# Viltrox_L132T_SAMD_Upgrade.net
KiCad netlist of a schematic drawn in EAGLE
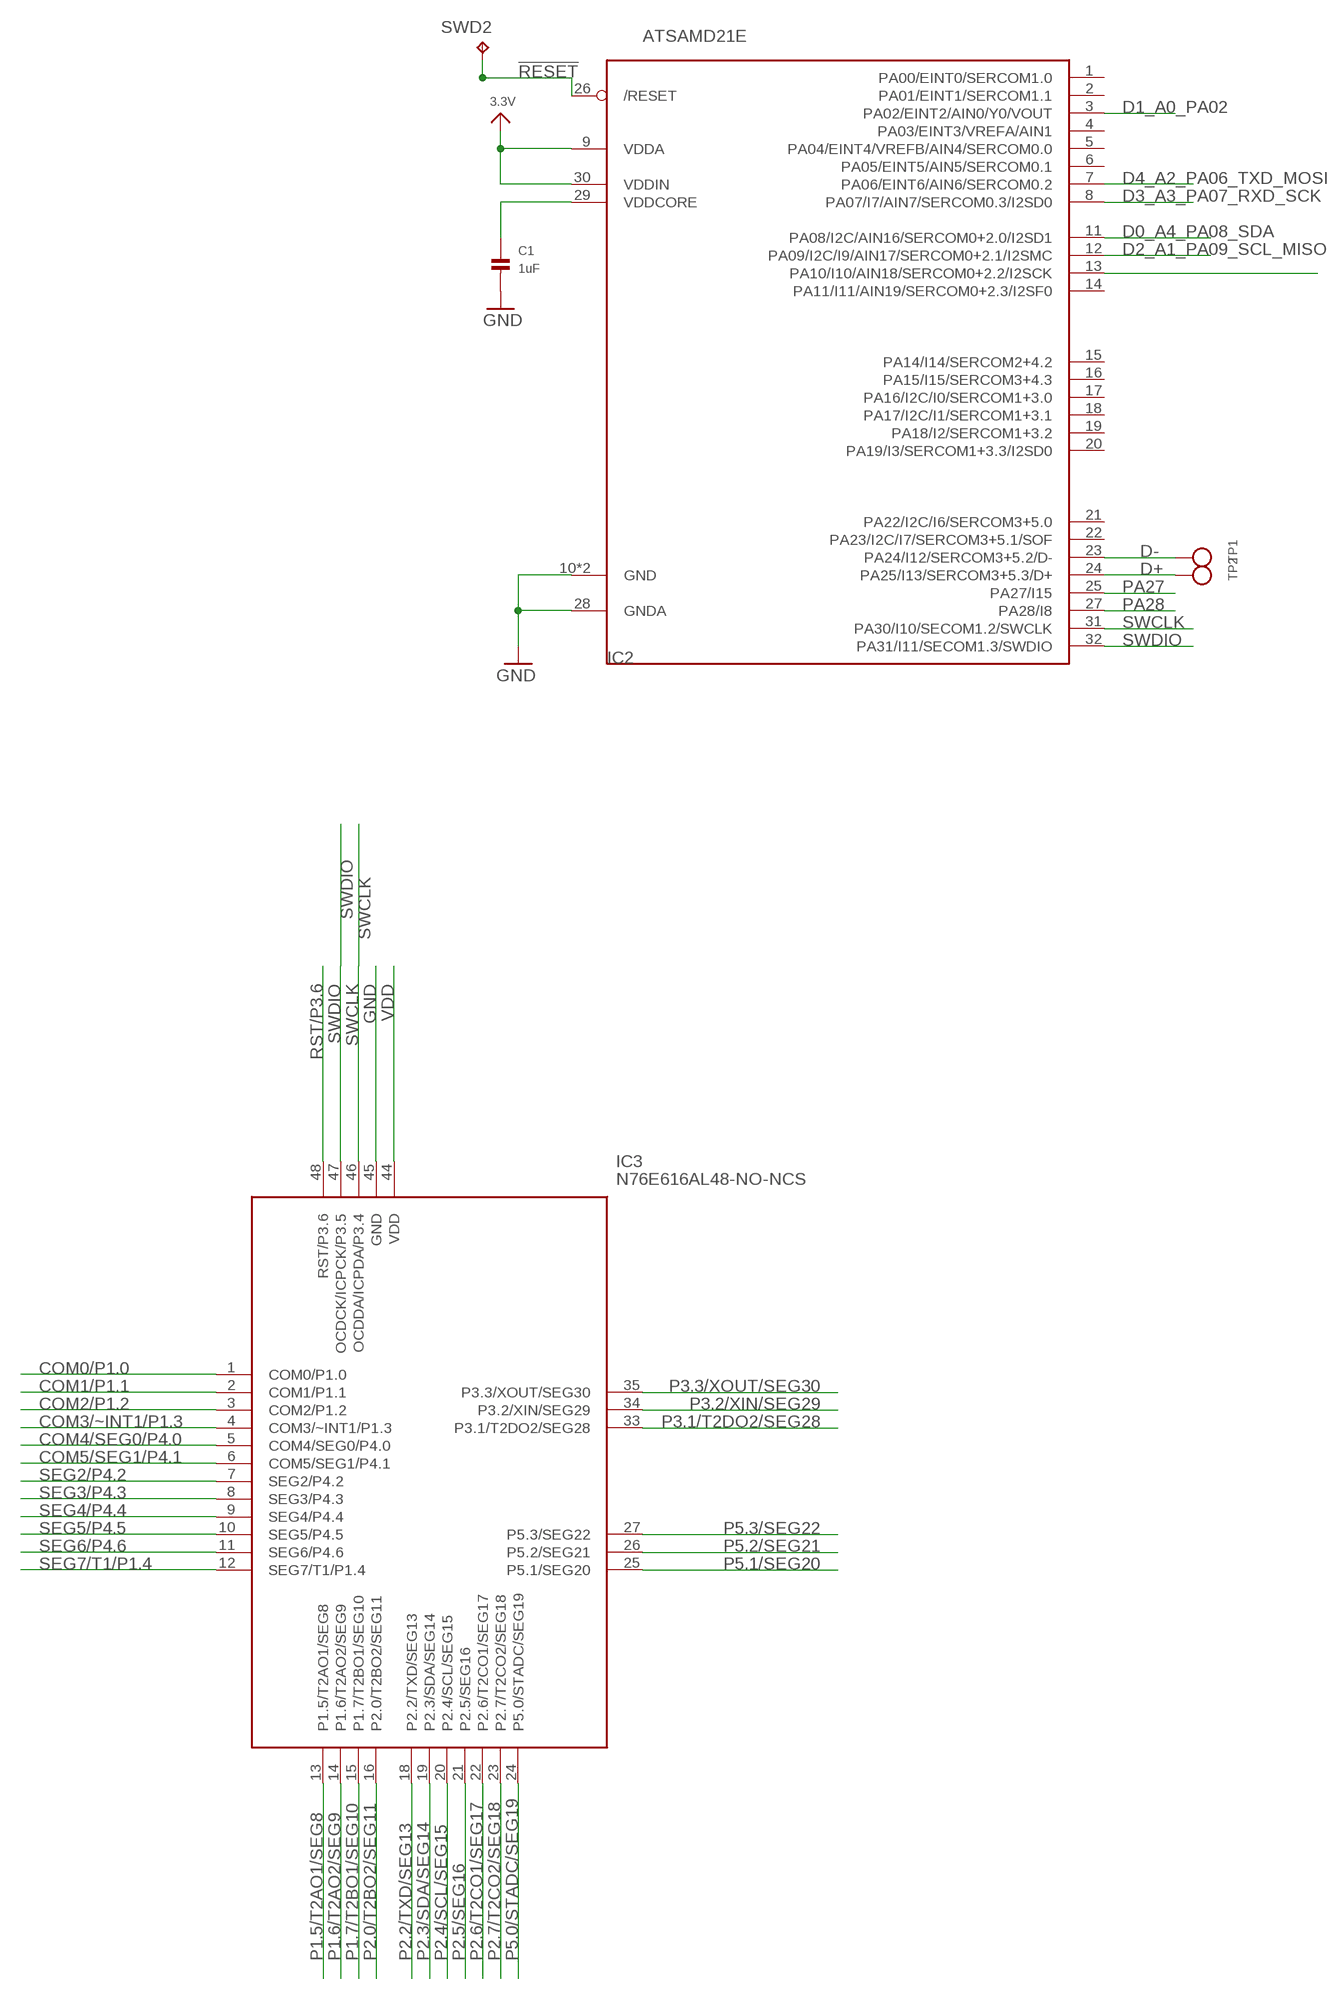
[diagram p0: schematic, sheet 1]

(export (version "E")
  (design (tool "Eeschema 10.0.6"))
  (components
    (comp (ref "C1")
      (value "1uF")
      (footprint "eagle-import:_0402MP")
      (libsource (lib "eagle-import") (part "CAP_CERAMIC_0402MP"))
    )
    (comp (ref "IC2")
      (value "ATSAMD21E")
      (footprint "eagle-import:QFN32_5MM")
      (libsource (lib "eagle-import") (part "ATSAMD21E"))
    )
    (comp (ref "IC3")
      (value "N76E616AL48-NO-NCS")
      (footprint "eagle-import:N76-NO-NC-QFP50P900X900X160-48N")
      (libsource (lib "eagle-import") (part "N76E616AL48-NO-NCS"))
    )
    (comp (ref "SWD2")
      (value "TPB1,27")
      (footprint "eagle-import:B1,27")
      (libsource (lib "eagle-import") (part "TPB1,27"))
    )
    (comp (ref "TP1")
      (value "TESTPOINTROUND2MM")
      (footprint "eagle-import:TESTPOINT_ROUND_2MM")
      (libsource (lib "eagle-import") (part "TESTPOINTROUND2MM"))
    )
    (comp (ref "TP2")
      (value "TESTPOINTROUND2MM")
      (footprint "eagle-import:TESTPOINT_ROUND_2MM")
      (libsource (lib "eagle-import") (part "TESTPOINTROUND2MM"))
    )
  )
  (nets
    (net (code "1") (name "/COM0{slash}P1.0") (class "Default")
      (node (ref "IC3") (pin "1") (pinfunction "COM0/P1.0_1") (pintype "bidirectional"))
    )
    (net (code "2") (name "/COM1{slash}P1.1") (class "Default")
      (node (ref "IC3") (pin "2") (pinfunction "COM1/P1.1_2") (pintype "bidirectional"))
    )
    (net (code "3") (name "/COM2{slash}P1.2") (class "Default")
      (node (ref "IC3") (pin "3") (pinfunction "COM2/P1.2_3") (pintype "bidirectional"))
    )
    (net (code "4") (name "/COM3{slash}~{INT1{slash}P1.3}") (class "Default")
      (node (ref "IC3") (pin "4") (pinfunction "COM3/~{INT1/P1.3}_4") (pintype "bidirectional"))
    )
    (net (code "5") (name "/COM4{slash}SEG0{slash}P4.0") (class "Default")
      (node (ref "IC3") (pin "5") (pinfunction "COM4/SEG0/P4.0_5") (pintype "bidirectional"))
    )
    (net (code "6") (name "/COM5{slash}SEG1{slash}P4.1") (class "Default")
      (node (ref "IC3") (pin "6") (pinfunction "COM5/SEG1/P4.1_6") (pintype "bidirectional"))
    )
    (net (code "7") (name "/D+") (class "Default")
      (node (ref "IC2") (pin "24") (pinfunction "PA25/I13/SERCOM3+5.3/D+_24") (pintype "bidirectional"))
      (node (ref "TP2") (pin "P$1") (pinfunction "P$1_P$1") (pintype "bidirectional"))
    )
    (net (code "8") (name "/D-") (class "Default")
      (node (ref "IC2") (pin "23") (pinfunction "PA24/I12/SERCOM3+5.2/D-_23") (pintype "bidirectional"))
      (node (ref "TP1") (pin "P$1") (pinfunction "P$1_P$1") (pintype "bidirectional"))
    )
    (net (code "9") (name "/D0_A4_PA08_SDA") (class "Default")
      (node (ref "IC2") (pin "11") (pinfunction "PA08/I2C/AIN16/SERCOM0+2.0/I2SD1_11") (pintype "bidirectional"))
    )
    (net (code "10") (name "/D1_A0_PA02") (class "Default")
      (node (ref "IC2") (pin "3") (pinfunction "PA02/EINT2/AIN0/Y0/VOUT_3") (pintype "bidirectional"))
    )
    (net (code "11") (name "/D2_A1_PA09_SCL_MISO") (class "Default")
      (node (ref "IC2") (pin "12") (pinfunction "PA09/I2C/I9/AIN17/SERCOM0+2.1/I2SMC_12") (pintype "bidirectional"))
    )
    (net (code "12") (name "/D3_A3_PA07_RXD_SCK") (class "Default")
      (node (ref "IC2") (pin "8") (pinfunction "PA07/I7/AIN7/SERCOM0.3/I2SD0_8") (pintype "bidirectional"))
    )
    (net (code "13") (name "/D4_A2_PA06_TXD_MOSI") (class "Default")
      (node (ref "IC2") (pin "7") (pinfunction "PA06/EINT6/AIN6/SERCOM0.2_7") (pintype "bidirectional"))
    )
    (net (code "14") (name "/P1.5{slash}T2AO1{slash}SEG8") (class "Default")
      (node (ref "IC3") (pin "13") (pinfunction "P1.5/T2AO1/SEG8_13") (pintype "bidirectional"))
    )
    (net (code "15") (name "/P1.6{slash}T2AO2{slash}SEG9") (class "Default")
      (node (ref "IC3") (pin "14") (pinfunction "P1.6/T2AO2/SEG9_14") (pintype "bidirectional"))
    )
    (net (code "16") (name "/P1.7{slash}T2BO1{slash}SEG10") (class "Default")
      (node (ref "IC3") (pin "15") (pinfunction "P1.7/T2BO1/SEG10_15") (pintype "bidirectional"))
    )
    (net (code "17") (name "/P2.0{slash}T2BO2{slash}SEG11") (class "Default")
      (node (ref "IC3") (pin "16") (pinfunction "P2.0/T2BO2/SEG11_16") (pintype "bidirectional"))
    )
    (net (code "18") (name "/P2.2{slash}TXD{slash}SEG13") (class "Default")
      (node (ref "IC3") (pin "18") (pinfunction "P2.2/TXD/SEG13_18") (pintype "bidirectional"))
    )
    (net (code "19") (name "/P2.3{slash}SDA{slash}SEG14") (class "Default")
      (node (ref "IC3") (pin "19") (pinfunction "P2.3/SDA/SEG14_19") (pintype "bidirectional"))
    )
    (net (code "20") (name "/P2.4{slash}SCL{slash}SEG15") (class "Default")
      (node (ref "IC3") (pin "20") (pinfunction "P2.4/SCL/SEG15_20") (pintype "bidirectional"))
    )
    (net (code "21") (name "/P2.5{slash}SEG16") (class "Default")
      (node (ref "IC3") (pin "21") (pinfunction "P2.5/SEG16_21") (pintype "bidirectional"))
    )
    (net (code "22") (name "/P2.6{slash}T2CO1{slash}SEG17") (class "Default")
      (node (ref "IC3") (pin "22") (pinfunction "P2.6/T2CO1/SEG17_22") (pintype "bidirectional"))
    )
    (net (code "23") (name "/P2.7{slash}T2CO2{slash}SEG18") (class "Default")
      (node (ref "IC3") (pin "23") (pinfunction "P2.7/T2CO2/SEG18_23") (pintype "bidirectional"))
    )
    (net (code "24") (name "/P3.1{slash}T2DO2{slash}SEG28") (class "Default")
      (node (ref "IC3") (pin "33") (pinfunction "P3.1/T2DO2/SEG28_33") (pintype "bidirectional"))
    )
    (net (code "25") (name "/P3.2{slash}XIN{slash}SEG29") (class "Default")
      (node (ref "IC3") (pin "34") (pinfunction "P3.2/XIN/SEG29_34") (pintype "bidirectional"))
    )
    (net (code "26") (name "/P3.3{slash}XOUT{slash}SEG30") (class "Default")
      (node (ref "IC3") (pin "35") (pinfunction "P3.3/XOUT/SEG30_35") (pintype "bidirectional"))
    )
    (net (code "27") (name "/P5.0{slash}STADC{slash}SEG19") (class "Default")
      (node (ref "IC3") (pin "24") (pinfunction "P5.0/STADC/SEG19_24") (pintype "bidirectional"))
    )
    (net (code "28") (name "/P5.1{slash}SEG20") (class "Default")
      (node (ref "IC3") (pin "25") (pinfunction "P5.1/SEG20_25") (pintype "bidirectional"))
    )
    (net (code "29") (name "/P5.2{slash}SEG21") (class "Default")
      (node (ref "IC3") (pin "26") (pinfunction "P5.2/SEG21_26") (pintype "bidirectional"))
    )
    (net (code "30") (name "/P5.3{slash}SEG22") (class "Default")
      (node (ref "IC3") (pin "27") (pinfunction "P5.3/SEG22_27") (pintype "bidirectional"))
    )
    (net (code "31") (name "/PA27") (class "Default")
      (node (ref "IC2") (pin "25") (pinfunction "PA27/I15_25") (pintype "bidirectional"))
    )
    (net (code "32") (name "/PA28") (class "Default")
      (node (ref "IC2") (pin "27") (pinfunction "PA28/I8_27") (pintype "bidirectional"))
    )
    (net (code "33") (name "/RST{slash}P3.6") (class "Default")
      (node (ref "IC3") (pin "48") (pinfunction "RST/P3.6_48") (pintype "bidirectional"))
    )
    (net (code "34") (name "/SEG2{slash}P4.2") (class "Default")
      (node (ref "IC3") (pin "7") (pinfunction "SEG2/P4.2_7") (pintype "bidirectional"))
    )
    (net (code "35") (name "/SEG3{slash}P4.3") (class "Default")
      (node (ref "IC3") (pin "8") (pinfunction "SEG3/P4.3_8") (pintype "bidirectional"))
    )
    (net (code "36") (name "/SEG4{slash}P4.4") (class "Default")
      (node (ref "IC3") (pin "9") (pinfunction "SEG4/P4.4_9") (pintype "bidirectional"))
    )
    (net (code "37") (name "/SEG5{slash}P4.5") (class "Default")
      (node (ref "IC3") (pin "10") (pinfunction "SEG5/P4.5_10") (pintype "bidirectional"))
    )
    (net (code "38") (name "/SEG6{slash}P4.6") (class "Default")
      (node (ref "IC3") (pin "11") (pinfunction "SEG6/P4.6_11") (pintype "bidirectional"))
    )
    (net (code "39") (name "/SEG7{slash}T1{slash}P1.4") (class "Default")
      (node (ref "IC3") (pin "12") (pinfunction "SEG7/T1/P1.4_12") (pintype "bidirectional"))
    )
    (net (code "40") (name "/SWCLK") (class "Default")
      (node (ref "IC2") (pin "31") (pinfunction "PA30/I10/SECOM1.2/SWCLK_31") (pintype "bidirectional"))
      (node (ref "IC3") (pin "46") (pinfunction "OCDDA/ICPDA/P3.4_46") (pintype "bidirectional"))
    )
    (net (code "41") (name "/SWDIO") (class "Default")
      (node (ref "IC2") (pin "32") (pinfunction "PA31/I11/SECOM1.3/SWDIO_32") (pintype "bidirectional"))
      (node (ref "IC3") (pin "47") (pinfunction "OCDCK/ICPCK/P3.5_47") (pintype "bidirectional"))
    )
    (net (code "42") (name "/VDD") (class "Default")
      (node (ref "IC3") (pin "44") (pinfunction "VDD_44") (pintype "bidirectional"))
    )
    (net (code "43") (name "/~{RESET}") (class "Default")
      (node (ref "IC2") (pin "26") (pinfunction "/RESET_26") (pintype "bidirectional"))
      (node (ref "SWD2") (pin "TP") (pinfunction "TP_TP") (pintype "input"))
    )
    (net (code "44") (name "3.3V") (class "Default")
      (node (ref "IC2") (pin "30") (pinfunction "VDDIN_30") (pintype "power_in"))
      (node (ref "IC2") (pin "9") (pinfunction "VDDA_9") (pintype "power_in"))
    )
    (net (code "45") (name "GND") (class "Default")
      (node (ref "C1") (pin "2") (pinfunction "P$2_2") (pintype "passive"))
      (node (ref "IC2") (pin "10") (pinfunction "GND_10") (pintype "power_in"))
      (node (ref "IC2") (pin "28") (pinfunction "GNDA_28") (pintype "power_in"))
      (node (ref "IC2") (pin "33") (pinfunction "GND_33") (pintype "power_in"))
      (node (ref "IC3") (pin "45") (pinfunction "GND_45") (pintype "bidirectional"))
    )
    (net (code "46") (name "Net-(C1-P$1)") (class "Default")
      (node (ref "C1") (pin "1") (pinfunction "P$1_1") (pintype "passive"))
      (node (ref "IC2") (pin "29") (pinfunction "VDDCORE_29") (pintype "power_in"))
    )
    (net (code "47") (name "unconnected-(IC2-PA00{slash}EINT0{slash}SERCOM1.0-Pad1)") (class "Default")
      (node (ref "IC2") (pin "1") (pinfunction "PA00/EINT0/SERCOM1.0_1") (pintype "bidirectional"))
    )
    (net (code "48") (name "unconnected-(IC2-PA01{slash}EINT1{slash}SERCOM1.1-Pad2)") (class "Default")
      (node (ref "IC2") (pin "2") (pinfunction "PA01/EINT1/SERCOM1.1_2") (pintype "bidirectional"))
    )
    (net (code "49") (name "unconnected-(IC2-PA03{slash}EINT3{slash}VREFA{slash}AIN1-Pad4)") (class "Default")
      (node (ref "IC2") (pin "4") (pinfunction "PA03/EINT3/VREFA/AIN1_4") (pintype "bidirectional"))
    )
    (net (code "50") (name "unconnected-(IC2-PA04{slash}EINT4{slash}VREFB{slash}AIN4{slash}SERCOM0.0-Pad5)") (class "Default")
      (node (ref "IC2") (pin "5") (pinfunction "PA04/EINT4/VREFB/AIN4/SERCOM0.0_5") (pintype "bidirectional"))
    )
    (net (code "51") (name "unconnected-(IC2-PA05{slash}EINT5{slash}AIN5{slash}SERCOM0.1-Pad6)") (class "Default")
      (node (ref "IC2") (pin "6") (pinfunction "PA05/EINT5/AIN5/SERCOM0.1_6") (pintype "bidirectional"))
    )
    (net (code "52") (name "unconnected-(IC2-PA10{slash}I10{slash}AIN18{slash}SERCOM0+2.2{slash}I2SCK-Pad13)") (class "Default")
      (node (ref "IC2") (pin "13") (pinfunction "PA10/I10/AIN18/SERCOM0+2.2/I2SCK_13") (pintype "bidirectional"))
    )
    (net (code "53") (name "unconnected-(IC2-PA11{slash}I11{slash}AIN19{slash}SERCOM0+2.3{slash}I2SF0-Pad14)") (class "Default")
      (node (ref "IC2") (pin "14") (pinfunction "PA11/I11/AIN19/SERCOM0+2.3/I2SF0_14") (pintype "bidirectional"))
    )
    (net (code "54") (name "unconnected-(IC2-PA14{slash}I14{slash}SERCOM2+4.2-Pad15)") (class "Default")
      (node (ref "IC2") (pin "15") (pinfunction "PA14/I14/SERCOM2+4.2_15") (pintype "bidirectional"))
    )
    (net (code "55") (name "unconnected-(IC2-PA15{slash}I15{slash}SERCOM3+4.3-Pad16)") (class "Default")
      (node (ref "IC2") (pin "16") (pinfunction "PA15/I15/SERCOM3+4.3_16") (pintype "bidirectional"))
    )
    (net (code "56") (name "unconnected-(IC2-PA16{slash}I2C{slash}I0{slash}SERCOM1+3.0-Pad17)") (class "Default")
      (node (ref "IC2") (pin "17") (pinfunction "PA16/I2C/I0/SERCOM1+3.0_17") (pintype "bidirectional"))
    )
    (net (code "57") (name "unconnected-(IC2-PA17{slash}I2C{slash}I1{slash}SERCOM1+3.1-Pad18)") (class "Default")
      (node (ref "IC2") (pin "18") (pinfunction "PA17/I2C/I1/SERCOM1+3.1_18") (pintype "bidirectional"))
    )
    (net (code "58") (name "unconnected-(IC2-PA18{slash}I2{slash}SERCOM1+3.2-Pad19)") (class "Default")
      (node (ref "IC2") (pin "19") (pinfunction "PA18/I2/SERCOM1+3.2_19") (pintype "bidirectional"))
    )
    (net (code "59") (name "unconnected-(IC2-PA19{slash}I3{slash}SERCOM1+3.3{slash}I2SD0-Pad20)") (class "Default")
      (node (ref "IC2") (pin "20") (pinfunction "PA19/I3/SERCOM1+3.3/I2SD0_20") (pintype "bidirectional"))
    )
    (net (code "60") (name "unconnected-(IC2-PA22{slash}I2C{slash}I6{slash}SERCOM3+5.0-Pad21)") (class "Default")
      (node (ref "IC2") (pin "21") (pinfunction "PA22/I2C/I6/SERCOM3+5.0_21") (pintype "bidirectional"))
    )
    (net (code "61") (name "unconnected-(IC2-PA23{slash}I2C{slash}I7{slash}SERCOM3+5.1{slash}SOF-Pad22)") (class "Default")
      (node (ref "IC2") (pin "22") (pinfunction "PA23/I2C/I7/SERCOM3+5.1/SOF_22") (pintype "bidirectional"))
    )
  )
)
